# blm_ctrl_processor.net
KiCad netlist of a schematic drawn in Altium Designer
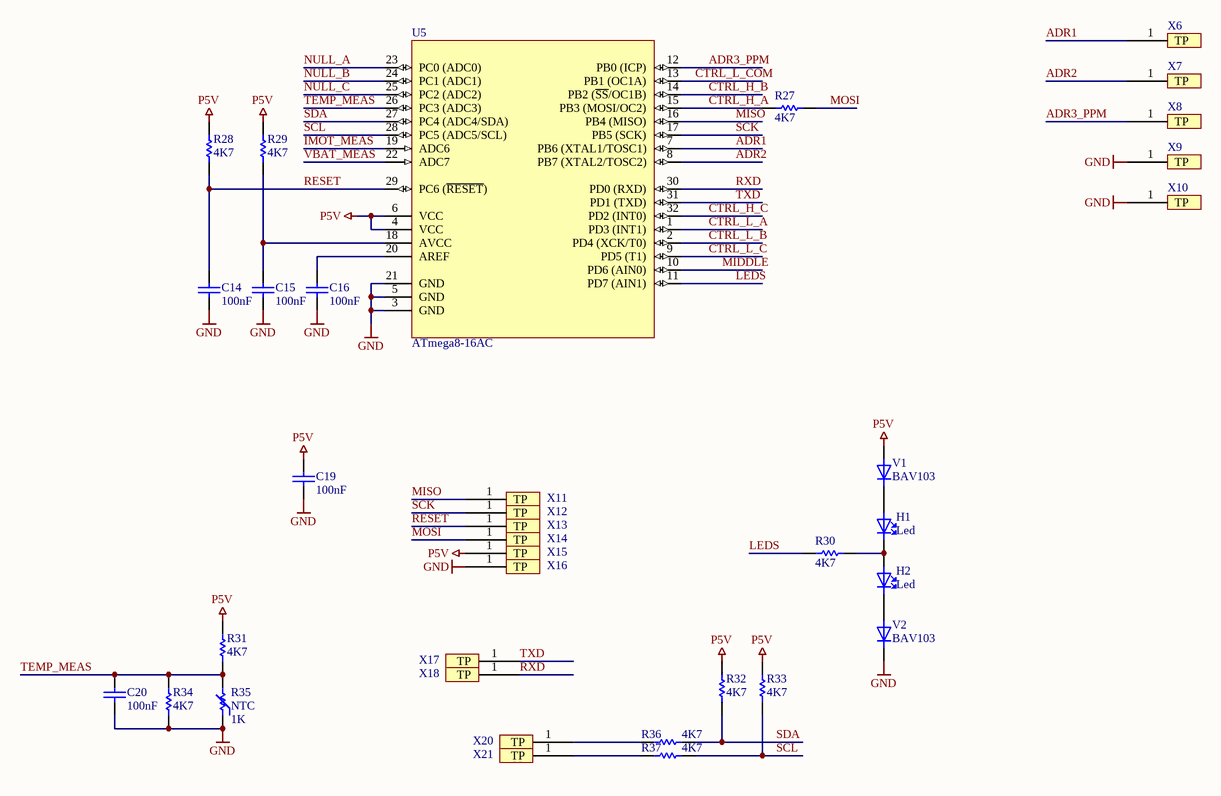
[diagram p0: blm_ctrl_processor.SchDoc]

(export (version "E")
  (design (tool "Eeschema 10.0.6"))
  (components
    (comp (ref "C14")
      (value "100nF")
      (footprint "0603")
      (description "Capacitor")
      (fields (field (name "Comment") "Cap") (field (name "PUBLISHER") "Altium Limited"))
      (libsource (lib "Miscellaneous Devices") (part "Cap"))
    )
    (comp (ref "C15")
      (value "100nF")
      (footprint "0603")
      (description "Capacitor")
      (fields (field (name "Comment") "Cap") (field (name "PUBLISHER") "Altium Limited"))
      (libsource (lib "Miscellaneous Devices") (part "Cap"))
    )
    (comp (ref "C16")
      (value "100nF")
      (footprint "0603")
      (description "Capacitor")
      (fields (field (name "Comment") "Cap") (field (name "PUBLISHER") "Altium Limited"))
      (libsource (lib "Miscellaneous Devices") (part "Cap"))
    )
    (comp (ref "C19")
      (value "100nF")
      (footprint "0603")
      (description "Capacitor")
      (fields (field (name "Comment") "Cap") (field (name "PUBLISHER") "Altium Limited"))
      (libsource (lib "Miscellaneous Devices") (part "Cap"))
    )
    (comp (ref "C20")
      (value "100nF")
      (footprint "0603")
      (description "Capacitor")
      (fields (field (name "Comment") "Cap") (field (name "PUBLISHER") "Altium Limited"))
      (libsource (lib "Miscellaneous Devices") (part "Cap"))
    )
    (comp (ref "H1")
      (value "Led")
      (footprint "0603_LED")
      (description "Led low current")
      (libsource (lib "RothLibrary") (part "Led"))
    )
    (comp (ref "H2")
      (value "Led")
      (footprint "0603_LED")
      (description "Led low current")
      (libsource (lib "RothLibrary") (part "Led"))
    )
    (comp (ref "R27")
      (value "4K7")
      (footprint "0603")
      (description "Resistor")
      (fields (field (name "Comment") "Res1") (field (name "PUBLISHER") "Altium Limited"))
      (libsource (lib "Miscellaneous Devices") (part "Res1"))
    )
    (comp (ref "R28")
      (value "4K7")
      (footprint "0603")
      (description "Resistor")
      (fields (field (name "Comment") "Res1") (field (name "PUBLISHER") "Altium Limited"))
      (libsource (lib "Miscellaneous Devices") (part "Res1"))
    )
    (comp (ref "R29")
      (value "4K7")
      (footprint "0603")
      (description "Resistor")
      (fields (field (name "Comment") "Res1") (field (name "PUBLISHER") "Altium Limited"))
      (libsource (lib "Miscellaneous Devices") (part "Res1"))
    )
    (comp (ref "R30")
      (value "4K7")
      (footprint "0603")
      (description "Resistor")
      (fields (field (name "Comment") "Res1") (field (name "PUBLISHER") "Altium Limited"))
      (libsource (lib "Miscellaneous Devices") (part "Res1"))
    )
    (comp (ref "R31")
      (value "4K7")
      (footprint "0603")
      (description "Resistor")
      (fields (field (name "Comment") "Res1") (field (name "PUBLISHER") "Altium Limited"))
      (libsource (lib "Miscellaneous Devices") (part "Res1"))
    )
    (comp (ref "R32")
      (value "4K7")
      (footprint "0603")
      (description "Resistor")
      (fields (field (name "Comment") "Res1") (field (name "PUBLISHER") "Altium Limited"))
      (libsource (lib "Miscellaneous Devices") (part "Res1"))
    )
    (comp (ref "R33")
      (value "4K7")
      (footprint "0603")
      (description "Resistor")
      (fields (field (name "Comment") "Res1") (field (name "PUBLISHER") "Altium Limited"))
      (libsource (lib "Miscellaneous Devices") (part "Res1"))
    )
    (comp (ref "R34")
      (value "4K7")
      (footprint "0603")
      (description "Resistor")
      (fields (field (name "Comment") "Res1") (field (name "PUBLISHER") "Altium Limited"))
      (libsource (lib "Miscellaneous Devices") (part "Res1"))
    )
    (comp (ref "R35")
      (value "NTC")
      (footprint "0603")
      (description "Temperature dependent resistor")
      (fields (field (name "ALTIUM_VALUE") "1K"))
      (libsource (lib "MyLibrary") (part "NTC"))
    )
    (comp (ref "R36")
      (value "4K7")
      (footprint "0603")
      (description "Resistor")
      (fields (field (name "Comment") "Res1") (field (name "PUBLISHER") "Altium Limited"))
      (libsource (lib "Miscellaneous Devices") (part "Res1"))
    )
    (comp (ref "R37")
      (value "4K7")
      (footprint "0603")
      (description "Resistor")
      (fields (field (name "Comment") "Res1") (field (name "PUBLISHER") "Altium Limited"))
      (libsource (lib "Miscellaneous Devices") (part "Res1"))
    )
    (comp (ref "U5")
      (value "ATmega8-16AC")
      (footprint "32A_L")
      (description "8-Bit AVR Microcontroller with 8K Bytes of In-System Programmable Flash Memory")
      (fields (field (name "PUBLISHER") "Altium Limited"))
      (libsource (lib "Atmel Microcontroller 8-Bit AVR") (part "ATmega8-16AC"))
    )
    (comp (ref "V1")
      (value "BAV103")
      (footprint "0603_LED")
      (description "Diode")
      (libsource (lib "RothLibrary") (part "Diode"))
    )
    (comp (ref "V2")
      (value "BAV103")
      (footprint "0603_LED")
      (description "Diode")
      (libsource (lib "RothLibrary") (part "Diode"))
    )
    (comp (ref "X6")
      (value "~")
      (footprint "PAD_SMD_0.5x1MM")
      (libsource (lib "MyLibrary") (part "TEST_POINT"))
    )
    (comp (ref "X7")
      (value "~")
      (footprint "PAD_SMD_0.5x1MM")
      (libsource (lib "MyLibrary") (part "TEST_POINT"))
    )
    (comp (ref "X8")
      (value "~")
      (footprint "PAD_SMD_0.5x1MM")
      (libsource (lib "MyLibrary") (part "TEST_POINT"))
    )
    (comp (ref "X9")
      (value "~")
      (footprint "PAD_SMD_0.5x1MM")
      (libsource (lib "MyLibrary") (part "TEST_POINT"))
    )
    (comp (ref "X10")
      (value "~")
      (footprint "PAD_SMD_0.5x1MM")
      (libsource (lib "MyLibrary") (part "TEST_POINT"))
    )
    (comp (ref "X11")
      (value "~")
      (footprint "PAD_SMD_1.5x2.5MM")
      (libsource (lib "MyLibrary") (part "TEST_POINT"))
    )
    (comp (ref "X12")
      (value "~")
      (footprint "PAD_SMD_1.5x2.5MM")
      (libsource (lib "MyLibrary") (part "TEST_POINT"))
    )
    (comp (ref "X13")
      (value "~")
      (footprint "PAD_SMD_1.5x2.5MM")
      (libsource (lib "MyLibrary") (part "TEST_POINT"))
    )
    (comp (ref "X14")
      (value "~")
      (footprint "PAD_SMD_1.5x2.5MM")
      (libsource (lib "MyLibrary") (part "TEST_POINT"))
    )
    (comp (ref "X15")
      (value "~")
      (footprint "PAD_SMD_1.5x2.5MM")
      (libsource (lib "MyLibrary") (part "TEST_POINT"))
    )
    (comp (ref "X16")
      (value "~")
      (footprint "PAD_SMD_1.5x2.5MM")
      (libsource (lib "MyLibrary") (part "TEST_POINT"))
    )
    (comp (ref "X17") (value "~") (footprint "PAD_SMD_1x2MM") (libsource (lib "") (part "TEST_POINT_1")))
    (comp (ref "X18") (value "~") (footprint "PAD_SMD_1x2MM") (libsource (lib "") (part "TEST_POINT_1")))
    (comp (ref "X20") (value "~") (footprint "PAD_SMD_1x2MM") (libsource (lib "") (part "TEST_POINT_1")))
    (comp (ref "X21") (value "~") (footprint "PAD_SMD_1x2MM") (libsource (lib "") (part "TEST_POINT_1")))
  )
  (nets
    (net (code "1") (name "/ADR1") (class "Default")
      (node (ref "U5") (pin "7") (pinfunction "PB6_(XTAL1/TOSC1)_7") (pintype "bidirectional"))
      (node (ref "X6") (pin "1") (pinfunction "TP_1") (pintype "passive"))
    )
    (net (code "2") (name "/ADR2") (class "Default")
      (node (ref "U5") (pin "8") (pinfunction "PB7_(XTAL2/TOSC2)_8") (pintype "bidirectional"))
      (node (ref "X7") (pin "1") (pinfunction "TP_1") (pintype "passive"))
    )
    (net (code "3") (name "/ADR3_PPM") (class "Default")
      (node (ref "U5") (pin "12") (pinfunction "PB0_(ICP)_12") (pintype "bidirectional"))
      (node (ref "X8") (pin "1") (pinfunction "TP_1") (pintype "passive"))
    )
    (net (code "4") (name "/CTRL_H_A") (class "Default")
      (node (ref "R27") (pin "2") (pinfunction "2_2") (pintype "passive"))
      (node (ref "U5") (pin "15") (pinfunction "PB3_(MOSI/OC2)_15") (pintype "bidirectional"))
    )
    (net (code "5") (name "/CTRL_H_B") (class "Default")
      (node (ref "U5") (pin "14") (pinfunction "PB2_(~{SS}/OC1B)_14") (pintype "bidirectional"))
    )
    (net (code "6") (name "/CTRL_H_C") (class "Default")
      (node (ref "U5") (pin "32") (pinfunction "PD2_(INT0)_32") (pintype "bidirectional"))
    )
    (net (code "7") (name "/CTRL_L_A") (class "Default")
      (node (ref "U5") (pin "1") (pinfunction "PD3_(INT1)_1") (pintype "bidirectional"))
    )
    (net (code "8") (name "/CTRL_L_B") (class "Default")
      (node (ref "U5") (pin "2") (pinfunction "PD4_(XCK/T0)_2") (pintype "bidirectional"))
    )
    (net (code "9") (name "/CTRL_L_C") (class "Default")
      (node (ref "U5") (pin "9") (pinfunction "PD5_(T1)_9") (pintype "bidirectional"))
    )
    (net (code "10") (name "/CTRL_L_COM") (class "Default")
      (node (ref "U5") (pin "13") (pinfunction "PB1_(OC1A)_13") (pintype "bidirectional"))
    )
    (net (code "11") (name "/IMOT_MEAS") (class "Default")
      (node (ref "U5") (pin "19") (pinfunction "ADC6_19") (pintype "input"))
    )
    (net (code "12") (name "/LEDS") (class "Default")
      (node (ref "R30") (pin "1") (pinfunction "1_1") (pintype "passive"))
      (node (ref "U5") (pin "11") (pinfunction "PD7_(AIN1)_11") (pintype "bidirectional"))
    )
    (net (code "13") (name "/MIDDLE") (class "Default")
      (node (ref "U5") (pin "10") (pinfunction "PD6_(AIN0)_10") (pintype "bidirectional"))
    )
    (net (code "14") (name "/MISO") (class "Default")
      (node (ref "U5") (pin "16") (pinfunction "PB4_(MISO)_16") (pintype "bidirectional"))
      (node (ref "X11") (pin "1") (pinfunction "TP_1") (pintype "passive"))
    )
    (net (code "15") (name "/MOSI") (class "Default")
      (node (ref "R27") (pin "1") (pinfunction "1_1") (pintype "passive"))
      (node (ref "X14") (pin "1") (pinfunction "TP_1") (pintype "passive"))
    )
    (net (code "16") (name "/NULL_A") (class "Default")
      (node (ref "U5") (pin "23") (pinfunction "PC0_(ADC0)_23") (pintype "bidirectional"))
    )
    (net (code "17") (name "/NULL_B") (class "Default")
      (node (ref "U5") (pin "24") (pinfunction "PC1_(ADC1)_24") (pintype "bidirectional"))
    )
    (net (code "18") (name "/NULL_C") (class "Default")
      (node (ref "U5") (pin "25") (pinfunction "PC2_(ADC2)_25") (pintype "bidirectional"))
    )
    (net (code "19") (name "/RESET") (class "Default")
      (node (ref "C14") (pin "1") (pinfunction "1_1") (pintype "passive"))
      (node (ref "R28") (pin "2") (pinfunction "2_2") (pintype "passive"))
      (node (ref "U5") (pin "29") (pinfunction "PC6_(~{RESET})_29") (pintype "bidirectional"))
      (node (ref "X13") (pin "1") (pinfunction "TP_1") (pintype "passive"))
    )
    (net (code "20") (name "/RXD") (class "Default")
      (node (ref "U5") (pin "30") (pinfunction "PD0_(RXD)_30") (pintype "bidirectional"))
      (node (ref "X18") (pin "1") (pinfunction "TP_1") (pintype "passive"))
    )
    (net (code "21") (name "/SCK") (class "Default")
      (node (ref "U5") (pin "17") (pinfunction "PB5_(SCK)_17") (pintype "bidirectional"))
      (node (ref "X12") (pin "1") (pinfunction "TP_1") (pintype "passive"))
    )
    (net (code "22") (name "/SCL") (class "Default")
      (node (ref "R33") (pin "2") (pinfunction "2_2") (pintype "passive"))
      (node (ref "R37") (pin "1") (pinfunction "1_1") (pintype "passive"))
      (node (ref "U5") (pin "28") (pinfunction "PC5_(ADC5/SCL)_28") (pintype "bidirectional"))
    )
    (net (code "23") (name "/SDA") (class "Default")
      (node (ref "R32") (pin "2") (pinfunction "2_2") (pintype "passive"))
      (node (ref "R36") (pin "1") (pinfunction "1_1") (pintype "passive"))
      (node (ref "U5") (pin "27") (pinfunction "PC4_(ADC4/SDA)_27") (pintype "bidirectional"))
    )
    (net (code "24") (name "/TEMP_MEAS") (class "Default")
      (node (ref "C20") (pin "1") (pinfunction "1_1") (pintype "passive"))
      (node (ref "R31") (pin "2") (pinfunction "2_2") (pintype "passive"))
      (node (ref "R34") (pin "1") (pinfunction "1_1") (pintype "passive"))
      (node (ref "R35") (pin "1") (pinfunction "1_1") (pintype "passive"))
      (node (ref "U5") (pin "26") (pinfunction "PC3_(ADC3)_26") (pintype "bidirectional"))
    )
    (net (code "25") (name "/TXD") (class "Default")
      (node (ref "U5") (pin "31") (pinfunction "PD1_(TXD)_31") (pintype "bidirectional"))
      (node (ref "X17") (pin "1") (pinfunction "TP_1") (pintype "passive"))
    )
    (net (code "26") (name "/VBAT_MEAS") (class "Default")
      (node (ref "U5") (pin "22") (pinfunction "ADC7_22") (pintype "input"))
    )
    (net (code "27") (name "GND") (class "Default")
      (node (ref "C14") (pin "2") (pinfunction "2_2") (pintype "passive"))
      (node (ref "C15") (pin "2") (pinfunction "2_2") (pintype "passive"))
      (node (ref "C16") (pin "2") (pinfunction "2_2") (pintype "passive"))
      (node (ref "C19") (pin "2") (pinfunction "2_2") (pintype "passive"))
      (node (ref "C20") (pin "2") (pinfunction "2_2") (pintype "passive"))
      (node (ref "R34") (pin "2") (pinfunction "2_2") (pintype "passive"))
      (node (ref "R35") (pin "2") (pinfunction "2_2") (pintype "passive"))
      (node (ref "U5") (pin "21") (pinfunction "GND_21") (pintype "power_in"))
      (node (ref "U5") (pin "3") (pinfunction "GND_3") (pintype "power_in"))
      (node (ref "U5") (pin "5") (pinfunction "GND_5") (pintype "power_in"))
      (node (ref "V2") (pin "2") (pinfunction "CATHODE_2") (pintype "passive"))
      (node (ref "X10") (pin "1") (pinfunction "TP_1") (pintype "passive"))
      (node (ref "X16") (pin "1") (pinfunction "TP_1") (pintype "passive"))
      (node (ref "X9") (pin "1") (pinfunction "TP_1") (pintype "passive"))
    )
    (net (code "28") (name "Net-(H1-ANODE)") (class "Default")
      (node (ref "H1") (pin "1") (pinfunction "ANODE_1") (pintype "passive"))
      (node (ref "V1") (pin "2") (pinfunction "CATHODE_2") (pintype "passive"))
    )
    (net (code "29") (name "Net-(H1-CATHODE)") (class "Default")
      (node (ref "H1") (pin "2") (pinfunction "CATHODE_2") (pintype "passive"))
      (node (ref "H2") (pin "1") (pinfunction "ANODE_1") (pintype "passive"))
      (node (ref "R30") (pin "2") (pinfunction "2_2") (pintype "passive"))
    )
    (net (code "30") (name "Net-(H2-CATHODE)") (class "Default")
      (node (ref "H2") (pin "2") (pinfunction "CATHODE_2") (pintype "passive"))
      (node (ref "V2") (pin "1") (pinfunction "ANODE_1") (pintype "passive"))
    )
    (net (code "31") (name "Net-(U5-AREF)") (class "Default")
      (node (ref "C16") (pin "1") (pinfunction "1_1") (pintype "passive"))
      (node (ref "U5") (pin "20") (pinfunction "AREF_20") (pintype "passive"))
    )
    (net (code "32") (name "Net-(U5-AVCC)") (class "Default")
      (node (ref "C15") (pin "1") (pinfunction "1_1") (pintype "passive"))
      (node (ref "R29") (pin "2") (pinfunction "2_2") (pintype "passive"))
      (node (ref "U5") (pin "18") (pinfunction "AVCC_18") (pintype "power_in"))
    )
    (net (code "33") (name "Net-(X20-TP)") (class "Default")
      (node (ref "R36") (pin "2") (pinfunction "2_2") (pintype "passive"))
      (node (ref "X20") (pin "1") (pinfunction "TP_1") (pintype "passive"))
    )
    (net (code "34") (name "Net-(X21-TP)") (class "Default")
      (node (ref "R37") (pin "2") (pinfunction "2_2") (pintype "passive"))
      (node (ref "X21") (pin "1") (pinfunction "TP_1") (pintype "passive"))
    )
    (net (code "35") (name "P5V") (class "Default")
      (node (ref "C19") (pin "1") (pinfunction "1_1") (pintype "passive"))
      (node (ref "R28") (pin "1") (pinfunction "1_1") (pintype "passive"))
      (node (ref "R29") (pin "1") (pinfunction "1_1") (pintype "passive"))
      (node (ref "R31") (pin "1") (pinfunction "1_1") (pintype "passive"))
      (node (ref "R32") (pin "1") (pinfunction "1_1") (pintype "passive"))
      (node (ref "R33") (pin "1") (pinfunction "1_1") (pintype "passive"))
      (node (ref "U5") (pin "4") (pinfunction "VCC_4") (pintype "power_in"))
      (node (ref "U5") (pin "6") (pinfunction "VCC_6") (pintype "power_in"))
      (node (ref "V1") (pin "1") (pinfunction "ANODE_1") (pintype "passive"))
      (node (ref "X15") (pin "1") (pinfunction "TP_1") (pintype "passive"))
    )
  )
)
